# POWER_SUPPLY.net
KiCad netlist of a schematic drawn in Altium Designer
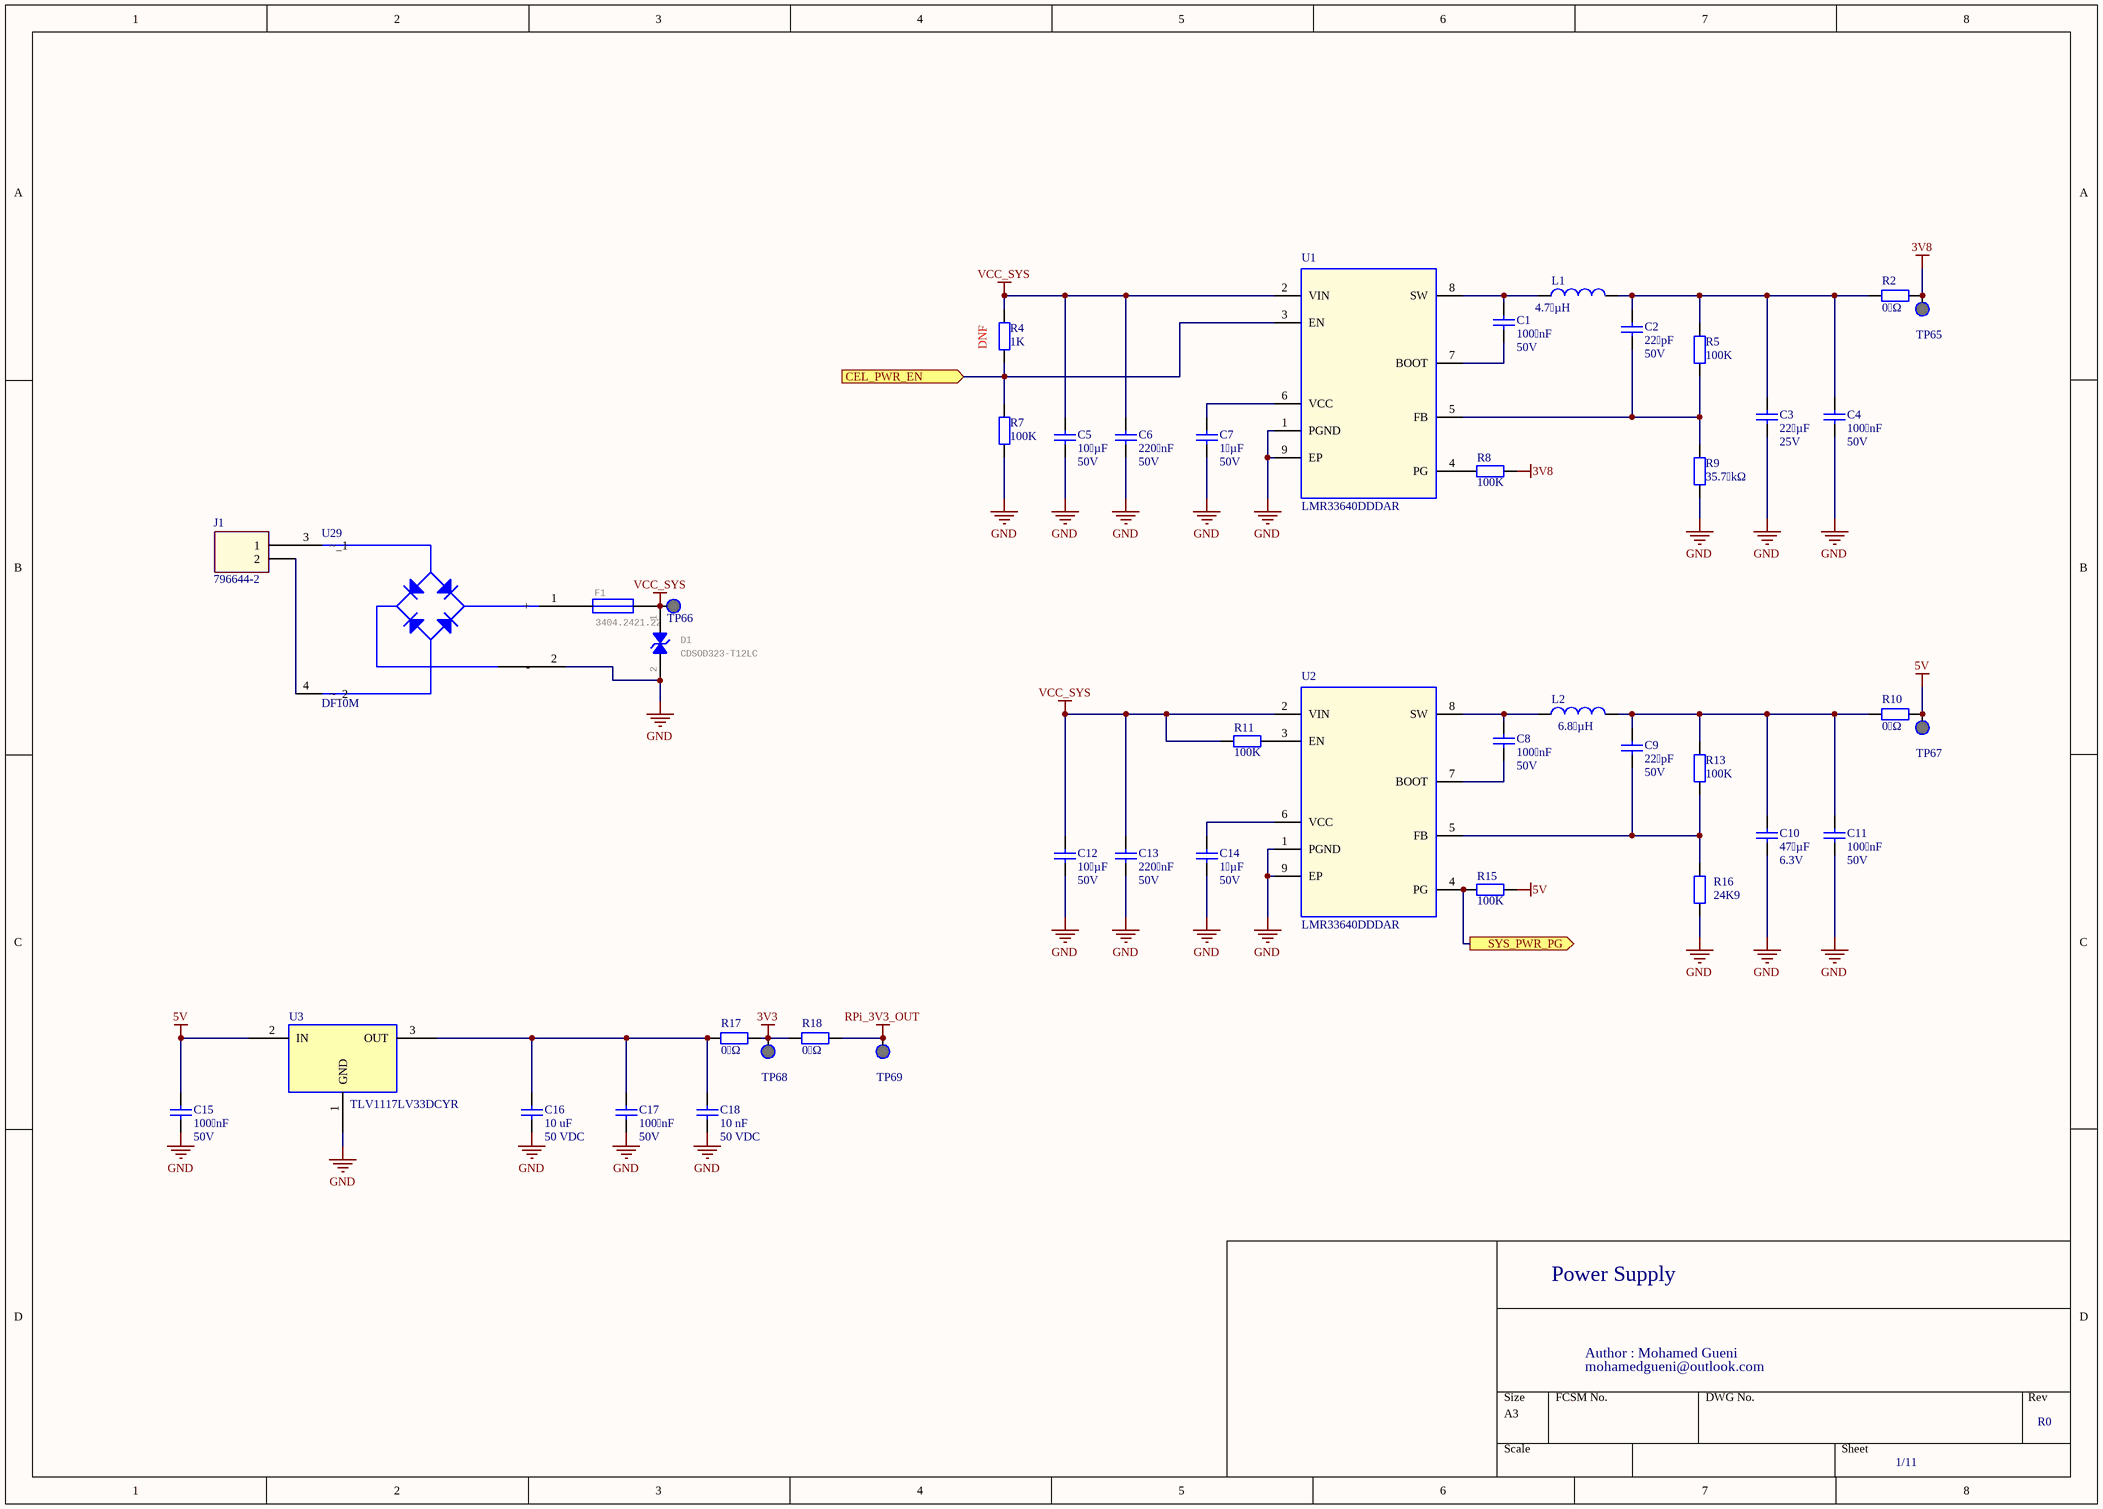
[diagram p0: POWER SUPPLY.SchDoc]

(export (version "E")
  (design (tool "Eeschema 10.0.6"))
  (components
    (comp (ref "C1")
      (value "Capacitor")
      (footprint "CAPC1608N")
      (fields
        (field (name "PART NUMBER") "CAP-000000017")
        (field (name "VALUE 1") "100 nF")
        (field (name "VALUE 2") "50V")
      )
      (libsource (lib "DB") (part "Capacitor"))
    )
    (comp (ref "C2")
      (value "Capacitor")
      (footprint "CAPC1608N")
      (fields
        (field (name "PART NUMBER") "CAP-000000027")
        (field (name "VALUE 1") "22 pF")
        (field (name "VALUE 2") "50V")
      )
      (libsource (lib "DB") (part "Capacitor"))
    )
    (comp (ref "C3")
      (value "Capacitor")
      (footprint "CAPC1608N")
      (fields
        (field (name "PART NUMBER") "CAP-000000024")
        (field (name "VALUE 1") "22 µF")
        (field (name "VALUE 2") "25V")
      )
      (libsource (lib "DB") (part "Capacitor"))
    )
    (comp (ref "C4")
      (value "Capacitor")
      (footprint "CAPC1608N")
      (fields
        (field (name "PART NUMBER") "CAP-000000017")
        (field (name "VALUE 1") "100 nF")
        (field (name "VALUE 2") "50V")
      )
      (libsource (lib "DB") (part "Capacitor"))
    )
    (comp (ref "C5")
      (value "Capacitor")
      (footprint "CAPC1608N")
      (fields
        (field (name "PART NUMBER") "CAP-000000025")
        (field (name "VALUE 1") "10 µF")
        (field (name "VALUE 2") "50V")
      )
      (libsource (lib "DB") (part "Capacitor"))
    )
    (comp (ref "C6")
      (value "Capacitor")
      (footprint "CAPC1608N")
      (fields
        (field (name "PART NUMBER") "CAP-000000026")
        (field (name "VALUE 1") "220 nF")
        (field (name "VALUE 2") "50V")
      )
      (libsource (lib "DB") (part "Capacitor"))
    )
    (comp (ref "C7")
      (value "Capacitor")
      (footprint "CAPC1608N")
      (fields
        (field (name "PART NUMBER") "CAP-000000018")
        (field (name "VALUE 1") "1 µF")
        (field (name "VALUE 2") "50V")
      )
      (libsource (lib "DB") (part "Capacitor"))
    )
    (comp (ref "C8")
      (value "Capacitor")
      (footprint "CAPC1608N")
      (fields
        (field (name "PART NUMBER") "CAP-000000017")
        (field (name "VALUE 1") "100 nF")
        (field (name "VALUE 2") "50V")
      )
      (libsource (lib "DB") (part "Capacitor"))
    )
    (comp (ref "C9")
      (value "Capacitor")
      (footprint "CAPC1608N")
      (fields
        (field (name "PART NUMBER") "CAP-000000027")
        (field (name "VALUE 1") "22 pF")
        (field (name "VALUE 2") "50V")
      )
      (libsource (lib "DB") (part "Capacitor"))
    )
    (comp (ref "C10")
      (value "T491D476K006AT")
      (footprint "CAPC1210")
      (fields
        (field (name "PART NUMBER") "CAP-000000029")
        (field (name "VALUE 1") "47 µF")
        (field (name "VALUE 2") "6.3V")
      )
      (libsource (lib "DB") (part "Capacitor"))
    )
    (comp (ref "C11")
      (value "Capacitor")
      (footprint "CAPC1608N")
      (fields
        (field (name "PART NUMBER") "CAP-000000017")
        (field (name "VALUE 1") "100 nF")
        (field (name "VALUE 2") "50V")
      )
      (libsource (lib "DB") (part "Capacitor"))
    )
    (comp (ref "C12")
      (value "Capacitor")
      (footprint "CAPC1608N")
      (fields
        (field (name "PART NUMBER") "CAP-000000025")
        (field (name "VALUE 1") "10 µF")
        (field (name "VALUE 2") "50V")
      )
      (libsource (lib "DB") (part "Capacitor"))
    )
    (comp (ref "C13")
      (value "Capacitor")
      (footprint "CAPC1608N")
      (fields
        (field (name "PART NUMBER") "CAP-000000026")
        (field (name "VALUE 1") "220 nF")
        (field (name "VALUE 2") "50V")
      )
      (libsource (lib "DB") (part "Capacitor"))
    )
    (comp (ref "C14")
      (value "Capacitor")
      (footprint "CAPC1608N")
      (fields
        (field (name "PART NUMBER") "CAP-000000018")
        (field (name "VALUE 1") "1 µF")
        (field (name "VALUE 2") "50V")
      )
      (libsource (lib "DB") (part "Capacitor"))
    )
    (comp (ref "C15")
      (value "Capacitor")
      (footprint "CAPC1608N")
      (fields
        (field (name "PART NUMBER") "CAP-000000017")
        (field (name "VALUE 1") "100 nF")
        (field (name "VALUE 2") "50V")
      )
      (libsource (lib "DB") (part "Capacitor"))
    )
    (comp (ref "C16")
      (value "GRM188R61E106MA73D")
      (footprint "CAPC1608N")
      (fields
        (field (name "PART NUMBER") "CAP-000000002")
        (field (name "VALUE 1") "10 uF")
        (field (name "VALUE 2") "50 VDC")
      )
      (libsource (lib "DB") (part "Capacitor"))
    )
    (comp (ref "C17")
      (value "Capacitor")
      (footprint "CAPC1608N")
      (fields
        (field (name "PART NUMBER") "CAP-000000017")
        (field (name "VALUE 1") "100 nF")
        (field (name "VALUE 2") "50V")
      )
      (libsource (lib "DB") (part "Capacitor"))
    )
    (comp (ref "C18")
      (value "C0603C103J5RACTU")
      (footprint "CAPC1608N")
      (fields
        (field (name "PART NUMBER") "CAP-000000006")
        (field (name "VALUE 1") "10 nF")
        (field (name "VALUE 2") "50 VDC")
      )
      (libsource (lib "DB") (part "Capacitor"))
    )
    (comp (ref "D1")
      (value "CDSOD323-T12LC")
      (footprint "CDSOD323T12LC")
      (fields (field (name "PART NUMBER") "TVS-000000003"))
      (libsource (lib "DB") (part "TVSBI"))
    )
    (comp (ref "F1")
      (value "3404.2421.22")
      (footprint "3404242122")
      (fields (field (name "PART NUMBER") "FU-000000001"))
      (libsource (lib "DB") (part "Fuse"))
    )
    (comp (ref "J1")
      (value "796644-2")
      (footprint "7966442")
      (fields (field (name "PART NUMBER") "CON-000000016"))
      (libsource (lib "DB") (part "HDRX2RIGHT"))
    )
    (comp (ref "L1")
      (value "XGL4030-472MEC")
      (footprint "1.5uH-XAL4020")
      (fields (field (name "PART NUMBER") "IND-000000003") (field (name "VALUE 1") "4.7 µH"))
      (libsource (lib "DB") (part "Inductor"))
    )
    (comp (ref "L2")
      (value "NRS4018T6R8MDGJ")
      (footprint "1.5uH-XAL4020")
      (fields (field (name "PART NUMBER") "IND-000000005") (field (name "VALUE 1") "6.8 µH"))
      (libsource (lib "DB") (part "Inductor"))
    )
    (comp (ref "R2")
      (value "Resistor")
      (footprint "RESC1608N")
      (fields (field (name "PART NUMBER") "RES-0000000017") (field (name "VALUE 1") "0 Ω"))
      (libsource (lib "") (part "Resistor_3"))
    )
    (comp (ref "R4")
      (value "Resistor")
      (footprint "RESC1608N")
      (fields (field (name "PART NUMBER") "RES-000000001") (field (name "VALUE 1") "1K"))
      (libsource (lib "") (part "Resistor_2"))
    )
    (comp (ref "R5")
      (value "Resistor")
      (footprint "RESC1608N")
      (fields (field (name "PART NUMBER") "RES-000000002") (field (name "VALUE 1") "100K"))
      (libsource (lib "DB") (part "Resistor"))
    )
    (comp (ref "R7")
      (value "Resistor")
      (footprint "RESC1608N")
      (fields (field (name "PART NUMBER") "RES-000000002") (field (name "VALUE 1") "100K"))
      (libsource (lib "") (part "Resistor_2"))
    )
    (comp (ref "R8")
      (value "Resistor")
      (footprint "RESC1608N")
      (fields (field (name "PART NUMBER") "RES-000000002") (field (name "VALUE 1") "100K"))
      (libsource (lib "") (part "Resistor_1"))
    )
    (comp (ref "R9")
      (value "Resistor")
      (footprint "RESC1608N")
      (fields (field (name "PART NUMBER") "RES-0000000016") (field (name "VALUE 1") "35.7 kΩ"))
      (libsource (lib "") (part "Resistor_2"))
    )
    (comp (ref "R10")
      (value "Resistor")
      (footprint "RESC1608N")
      (fields (field (name "PART NUMBER") "RES-0000000017") (field (name "VALUE 1") "0 Ω"))
      (libsource (lib "") (part "Resistor_3"))
    )
    (comp (ref "R11")
      (value "Resistor")
      (footprint "RESC1608N")
      (fields (field (name "PART NUMBER") "RES-000000002") (field (name "VALUE 1") "100K"))
      (libsource (lib "") (part "Resistor_1"))
    )
    (comp (ref "R13")
      (value "Resistor")
      (footprint "RESC1608N")
      (fields (field (name "PART NUMBER") "RES-000000002") (field (name "VALUE 1") "100K"))
      (libsource (lib "DB") (part "Resistor"))
    )
    (comp (ref "R15")
      (value "Resistor")
      (footprint "RESC1608N")
      (fields (field (name "PART NUMBER") "RES-000000002") (field (name "VALUE 1") "100K"))
      (libsource (lib "") (part "Resistor_1"))
    )
    (comp (ref "R16")
      (value "RN731JTTD2492F25")
      (footprint "RESC1608N")
      (fields (field (name "PART NUMBER") "RES-000000003") (field (name "VALUE 1") "24K9"))
      (libsource (lib "") (part "Resistor_2"))
    )
    (comp (ref "R17")
      (value "Resistor")
      (footprint "RESC1608N")
      (fields (field (name "PART NUMBER") "RES-0000000017") (field (name "VALUE 1") "0 Ω"))
      (libsource (lib "") (part "Resistor_3"))
    )
    (comp (ref "R18")
      (value "Resistor")
      (footprint "RESC1608N")
      (fields (field (name "PART NUMBER") "RES-0000000017") (field (name "VALUE 1") "0 Ω"))
      (libsource (lib "") (part "Resistor_3"))
    )
    (comp (ref "TP65")
      (value "Test Point")
      (footprint "TP")
      (fields (field (name "PART NUMBER") "MIS-000000002"))
      (libsource (lib "DB") (part "TP"))
    )
    (comp (ref "TP66")
      (value "Test Point")
      (footprint "TP")
      (fields (field (name "PART NUMBER") "MIS-000000002"))
      (libsource (lib "DB") (part "TP"))
    )
    (comp (ref "TP67")
      (value "Test Point")
      (footprint "TP")
      (fields (field (name "PART NUMBER") "MIS-000000002"))
      (libsource (lib "DB") (part "TP"))
    )
    (comp (ref "TP68")
      (value "Test Point")
      (footprint "TP")
      (fields (field (name "PART NUMBER") "MIS-000000002"))
      (libsource (lib "DB") (part "TP"))
    )
    (comp (ref "TP69")
      (value "Test Point")
      (footprint "TP")
      (fields (field (name "PART NUMBER") "MIS-000000002"))
      (libsource (lib "DB") (part "TP"))
    )
    (comp (ref "U1")
      (value "LMR33640DDDAR")
      (footprint "SOIC127P600X170-9N")
      (fields (field (name "PART NUMBER") "VRG-000000003"))
      (libsource (lib "DB") (part "LMR33640DDDAR"))
    )
    (comp (ref "U2")
      (value "LMR33640DDDAR")
      (footprint "SOIC127P600X170-9N")
      (fields (field (name "PART NUMBER") "VRG-000000003"))
      (libsource (lib "DB") (part "LMR33640DDDAR"))
    )
    (comp (ref "U3")
      (value "TLV1117LV33DCYR")
      (footprint "SOT-223-4")
      (fields (field (name "PART NUMBER") "VRG-000000001"))
      (libsource (lib "DB") (part "TLV1117"))
    )
    (comp (ref "U29")
      (value "DF10M")
      (footprint "621-DF10M")
      (fields (field (name "PART NUMBER") "VRG-000000002"))
      (libsource (lib "DB") (part "DF10M"))
    )
  )
  (nets
    (net (code "1") (name "/CEL_PWR_EN") (class "Default")
      (node (ref "R4") (pin "1") (pinfunction "1_1") (pintype "passive"))
      (node (ref "R7") (pin "2") (pinfunction "2_2") (pintype "passive"))
      (node (ref "U1") (pin "3") (pinfunction "EN_3") (pintype "passive"))
    )
    (net (code "2") (name "/SYS_PWR_PG") (class "Default")
      (node (ref "R15") (pin "2") (pinfunction "2_2") (pintype "passive"))
      (node (ref "U2") (pin "4") (pinfunction "PG_4") (pintype "passive"))
    )
    (net (code "3") (name "3V3") (class "Default")
      (node (ref "R17") (pin "2") (pinfunction "2_2") (pintype "passive"))
      (node (ref "R18") (pin "1") (pinfunction "1_1") (pintype "passive"))
      (node (ref "TP68") (pin "1") (pinfunction "1_1") (pintype "passive"))
    )
    (net (code "4") (name "3V8") (class "Default")
      (node (ref "R2") (pin "2") (pinfunction "2_2") (pintype "passive"))
      (node (ref "R8") (pin "1") (pinfunction "1_1") (pintype "passive"))
      (node (ref "TP65") (pin "1") (pinfunction "1_1") (pintype "passive"))
    )
    (net (code "5") (name "5V") (class "Default")
      (node (ref "C15") (pin "2") (pinfunction "2_2") (pintype "passive"))
      (node (ref "R10") (pin "2") (pinfunction "2_2") (pintype "passive"))
      (node (ref "R15") (pin "1") (pinfunction "1_1") (pintype "passive"))
      (node (ref "TP67") (pin "1") (pinfunction "1_1") (pintype "passive"))
      (node (ref "U3") (pin "2") (pinfunction "IN_2") (pintype "passive"))
    )
    (net (code "6") (name "GND") (class "Default")
      (node (ref "C10") (pin "1") (pinfunction "1_1") (pintype "passive"))
      (node (ref "C11") (pin "1") (pinfunction "1_1") (pintype "passive"))
      (node (ref "C12") (pin "1") (pinfunction "1_1") (pintype "passive"))
      (node (ref "C13") (pin "1") (pinfunction "1_1") (pintype "passive"))
      (node (ref "C14") (pin "1") (pinfunction "1_1") (pintype "passive"))
      (node (ref "C15") (pin "1") (pinfunction "1_1") (pintype "passive"))
      (node (ref "C16") (pin "1") (pinfunction "1_1") (pintype "passive"))
      (node (ref "C17") (pin "1") (pinfunction "1_1") (pintype "passive"))
      (node (ref "C18") (pin "1") (pinfunction "1_1") (pintype "passive"))
      (node (ref "C3") (pin "1") (pinfunction "1_1") (pintype "passive"))
      (node (ref "C4") (pin "1") (pinfunction "1_1") (pintype "passive"))
      (node (ref "C5") (pin "1") (pinfunction "1_1") (pintype "passive"))
      (node (ref "C6") (pin "1") (pinfunction "1_1") (pintype "passive"))
      (node (ref "C7") (pin "1") (pinfunction "1_1") (pintype "passive"))
      (node (ref "D1") (pin "2") (pinfunction "2_2") (pintype "passive"))
      (node (ref "R16") (pin "1") (pinfunction "1_1") (pintype "passive"))
      (node (ref "R7") (pin "1") (pinfunction "1_1") (pintype "passive"))
      (node (ref "R9") (pin "1") (pinfunction "1_1") (pintype "passive"))
      (node (ref "U1") (pin "1") (pinfunction "PGND_1") (pintype "passive"))
      (node (ref "U1") (pin "9") (pinfunction "EP_9") (pintype "passive"))
      (node (ref "U2") (pin "1") (pinfunction "PGND_1") (pintype "passive"))
      (node (ref "U2") (pin "9") (pinfunction "EP_9") (pintype "passive"))
      (node (ref "U29") (pin "2") (pinfunction "-_2") (pintype "passive"))
      (node (ref "U3") (pin "1") (pinfunction "GND_1") (pintype "passive"))
    )
    (net (code "7") (name "Net-(C2-Pad2)") (class "Default")
      (node (ref "C2") (pin "2") (pinfunction "2_2") (pintype "passive"))
      (node (ref "C3") (pin "2") (pinfunction "2_2") (pintype "passive"))
      (node (ref "C4") (pin "2") (pinfunction "2_2") (pintype "passive"))
      (node (ref "L1") (pin "2") (pinfunction "2_2") (pintype "passive"))
      (node (ref "R2") (pin "1") (pinfunction "1_1") (pintype "passive"))
      (node (ref "R5") (pin "1") (pinfunction "1_1") (pintype "passive"))
    )
    (net (code "8") (name "Net-(C10-Pad2)") (class "Default")
      (node (ref "C10") (pin "2") (pinfunction "2_2") (pintype "passive"))
      (node (ref "C11") (pin "2") (pinfunction "2_2") (pintype "passive"))
      (node (ref "C9") (pin "2") (pinfunction "2_2") (pintype "passive"))
      (node (ref "L2") (pin "2") (pinfunction "2_2") (pintype "passive"))
      (node (ref "R10") (pin "1") (pinfunction "1_1") (pintype "passive"))
      (node (ref "R13") (pin "1") (pinfunction "1_1") (pintype "passive"))
    )
    (net (code "9") (name "Net-(U1-BOOT)") (class "Default")
      (node (ref "C1") (pin "1") (pinfunction "1_1") (pintype "passive"))
      (node (ref "U1") (pin "7") (pinfunction "BOOT_7") (pintype "passive"))
    )
    (net (code "10") (name "Net-(U1-FB)") (class "Default")
      (node (ref "C2") (pin "1") (pinfunction "1_1") (pintype "passive"))
      (node (ref "R5") (pin "2") (pinfunction "2_2") (pintype "passive"))
      (node (ref "R9") (pin "2") (pinfunction "2_2") (pintype "passive"))
      (node (ref "U1") (pin "5") (pinfunction "FB_5") (pintype "passive"))
    )
    (net (code "11") (name "Net-(U1-PG)") (class "Default")
      (node (ref "R8") (pin "2") (pinfunction "2_2") (pintype "passive"))
      (node (ref "U1") (pin "4") (pinfunction "PG_4") (pintype "passive"))
    )
    (net (code "12") (name "Net-(U1-SW)") (class "Default")
      (node (ref "C1") (pin "2") (pinfunction "2_2") (pintype "passive"))
      (node (ref "L1") (pin "1") (pinfunction "1_1") (pintype "passive"))
      (node (ref "U1") (pin "8") (pinfunction "SW_8") (pintype "passive"))
    )
    (net (code "13") (name "Net-(U1-VCC)") (class "Default")
      (node (ref "C7") (pin "2") (pinfunction "2_2") (pintype "passive"))
      (node (ref "U1") (pin "6") (pinfunction "VCC_6") (pintype "passive"))
    )
    (net (code "14") (name "Net-(U2-BOOT)") (class "Default")
      (node (ref "C8") (pin "1") (pinfunction "1_1") (pintype "passive"))
      (node (ref "U2") (pin "7") (pinfunction "BOOT_7") (pintype "passive"))
    )
    (net (code "15") (name "Net-(U2-EN)") (class "Default")
      (node (ref "R11") (pin "1") (pinfunction "1_1") (pintype "passive"))
      (node (ref "U2") (pin "3") (pinfunction "EN_3") (pintype "passive"))
    )
    (net (code "16") (name "Net-(U2-FB)") (class "Default")
      (node (ref "C9") (pin "1") (pinfunction "1_1") (pintype "passive"))
      (node (ref "R13") (pin "2") (pinfunction "2_2") (pintype "passive"))
      (node (ref "R16") (pin "2") (pinfunction "2_2") (pintype "passive"))
      (node (ref "U2") (pin "5") (pinfunction "FB_5") (pintype "passive"))
    )
    (net (code "17") (name "Net-(U2-SW)") (class "Default")
      (node (ref "C8") (pin "2") (pinfunction "2_2") (pintype "passive"))
      (node (ref "L2") (pin "1") (pinfunction "1_1") (pintype "passive"))
      (node (ref "U2") (pin "8") (pinfunction "SW_8") (pintype "passive"))
    )
    (net (code "18") (name "Net-(U2-VCC)") (class "Default")
      (node (ref "C14") (pin "2") (pinfunction "2_2") (pintype "passive"))
      (node (ref "U2") (pin "6") (pinfunction "VCC_6") (pintype "passive"))
    )
    (net (code "19") (name "Net-(U3-OUT)") (class "Default")
      (node (ref "C16") (pin "2") (pinfunction "2_2") (pintype "passive"))
      (node (ref "C17") (pin "2") (pinfunction "2_2") (pintype "passive"))
      (node (ref "C18") (pin "2") (pinfunction "2_2") (pintype "passive"))
      (node (ref "R17") (pin "1") (pinfunction "1_1") (pintype "passive"))
      (node (ref "U3") (pin "3") (pinfunction "OUT_3") (pintype "passive"))
    )
    (net (code "20") (name "Net-(U29-+)") (class "Default")
      (node (ref "F1") (pin "1") (pinfunction "1_1") (pintype "power_in"))
      (node (ref "U29") (pin "1") (pinfunction "+_1") (pintype "passive"))
    )
    (net (code "21") (name "Net-(U29-~_1)") (class "Default")
      (node (ref "J1") (pin "1") (pinfunction "1_1") (pintype "passive"))
      (node (ref "U29") (pin "3") (pinfunction "~_1_3") (pintype "passive"))
    )
    (net (code "22") (name "Net-(U29-~_2)") (class "Default")
      (node (ref "J1") (pin "2") (pinfunction "2_2") (pintype "passive"))
      (node (ref "U29") (pin "4") (pinfunction "~_2_4") (pintype "passive"))
    )
    (net (code "23") (name "RPi_3V3_OUT") (class "Default")
      (node (ref "R18") (pin "2") (pinfunction "2_2") (pintype "passive"))
      (node (ref "TP69") (pin "1") (pinfunction "1_1") (pintype "passive"))
    )
    (net (code "24") (name "VCC_SYS") (class "Default")
      (node (ref "C12") (pin "2") (pinfunction "2_2") (pintype "passive"))
      (node (ref "C13") (pin "2") (pinfunction "2_2") (pintype "passive"))
      (node (ref "C5") (pin "2") (pinfunction "2_2") (pintype "passive"))
      (node (ref "C6") (pin "2") (pinfunction "2_2") (pintype "passive"))
      (node (ref "D1") (pin "1") (pinfunction "1_1") (pintype "passive"))
      (node (ref "F1") (pin "2") (pinfunction "2_2") (pintype "power_in"))
      (node (ref "R11") (pin "2") (pinfunction "2_2") (pintype "passive"))
      (node (ref "R4") (pin "2") (pinfunction "2_2") (pintype "passive"))
      (node (ref "TP66") (pin "1") (pinfunction "1_1") (pintype "passive"))
      (node (ref "U1") (pin "2") (pinfunction "VIN_2") (pintype "passive"))
      (node (ref "U2") (pin "2") (pinfunction "VIN_2") (pintype "passive"))
    )
  )
)
